# RAK3172_board.net
KiCad netlist of a schematic drawn in EAGLE
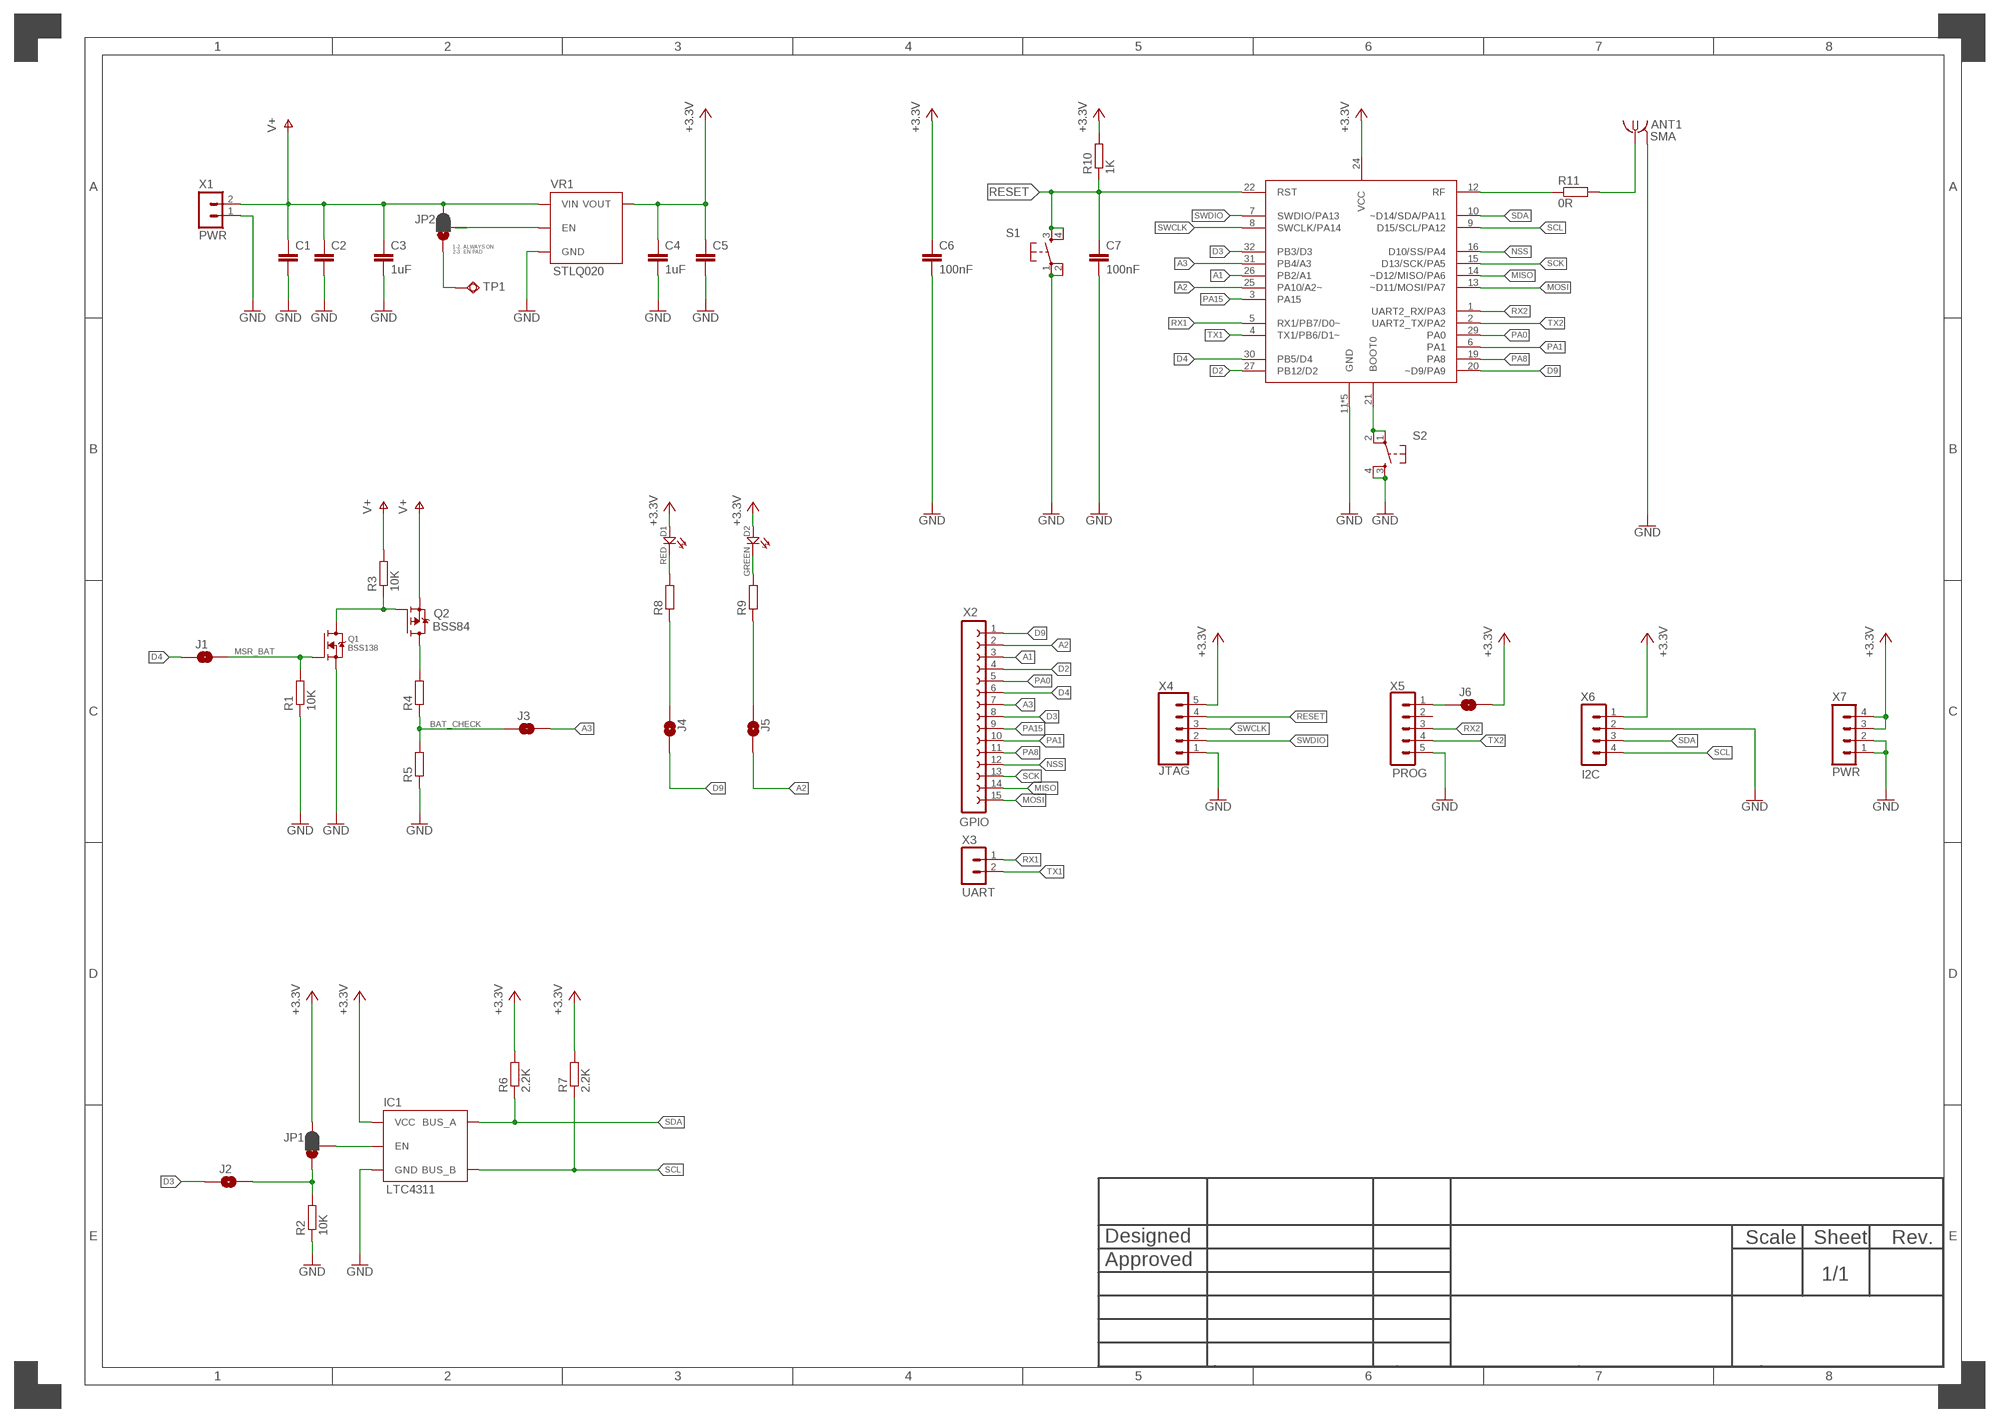
[diagram p0: schematic, sheet 1]

(export (version "E")
  (design (tool "Eeschema 10.0.6"))
  (components
    (comp (ref "ANT1")
      (value "SMA")
      (footprint "eagle-import:SMA_1MM")
      (libsource (lib "eagle-import") (part "SMA"))
    )
    (comp (ref "C1")
      (value "CAP_CERAMIC_0603")
      (footprint "eagle-import:SMD_0603C")
      (libsource (lib "eagle-import") (part "CAP_CERAMIC_0603"))
    )
    (comp (ref "C2")
      (value "CAP_CERAMIC_0603")
      (footprint "eagle-import:SMD_0603C")
      (libsource (lib "eagle-import") (part "CAP_CERAMIC_0603"))
    )
    (comp (ref "C3")
      (value "1uF")
      (footprint "eagle-import:SMD_0603C")
      (libsource (lib "eagle-import") (part "CAP_CERAMIC_0603"))
    )
    (comp (ref "C4")
      (value "1uF")
      (footprint "eagle-import:SMD_0603C")
      (libsource (lib "eagle-import") (part "CAP_CERAMIC_0603"))
    )
    (comp (ref "C5")
      (value "CAP_CERAMIC_0603")
      (footprint "eagle-import:SMD_0603C")
      (libsource (lib "eagle-import") (part "CAP_CERAMIC_0603"))
    )
    (comp (ref "C6")
      (value "100nF")
      (footprint "eagle-import:SMD_0603C")
      (libsource (lib "eagle-import") (part "CAP_CERAMIC_0603"))
    )
    (comp (ref "C7")
      (value "100nF")
      (footprint "eagle-import:SMD_0603C")
      (libsource (lib "eagle-import") (part "CAP_CERAMIC_0603"))
    )
    (comp (ref "D1")
      (value "RED")
      (footprint "eagle-import:LED-0805")
      (libsource (lib "eagle-import") (part "LED0805"))
    )
    (comp (ref "D2")
      (value "GREEN")
      (footprint "eagle-import:LED-0805")
      (libsource (lib "eagle-import") (part "LED0805"))
    )
    (comp (ref "IC1")
      (value "LTC4311")
      (footprint "eagle-import:SC-70-6")
      (libsource (lib "eagle-import") (part "LTC4311"))
    )
    (comp (ref "IC2")
      (value "RAK3172HF")
      (footprint "eagle-import:RAK3172")
      (libsource (lib "eagle-import") (part "RAK3172HF"))
    )
    (comp (ref "J1")
      (value "SMD_JUMP_2_NO_N")
      (footprint "eagle-import:SMT_JUMP_2_NO")
      (libsource (lib "eagle-import") (part "SMD_JUMP_2_NO_N"))
    )
    (comp (ref "J2")
      (value "SMD_JUMP_2_NO_N")
      (footprint "eagle-import:SMT_JUMP_2_NO")
      (libsource (lib "eagle-import") (part "SMD_JUMP_2_NO_N"))
    )
    (comp (ref "J3")
      (value "SMD_JUMP_2_NO_N")
      (footprint "eagle-import:SMT_JUMP_2_NO")
      (libsource (lib "eagle-import") (part "SMD_JUMP_2_NO_N"))
    )
    (comp (ref "J4")
      (value "SMD_JUMP_2_NO_N")
      (footprint "eagle-import:SMT_JUMP_2_NO")
      (libsource (lib "eagle-import") (part "SMD_JUMP_2_NO_N"))
    )
    (comp (ref "J5")
      (value "SMD_JUMP_2_NO_N")
      (footprint "eagle-import:SMT_JUMP_2_NO")
      (libsource (lib "eagle-import") (part "SMD_JUMP_2_NO_N"))
    )
    (comp (ref "J6")
      (value "SMD_JUMP_2_NO_N")
      (footprint "eagle-import:SMT_JUMP_2_NO")
      (libsource (lib "eagle-import") (part "SMD_JUMP_2_NO_N"))
    )
    (comp (ref "JP1")
      (value "JUMPER-SMT_3_1-NC_PASTE_SILK")
      (footprint "eagle-import:SMT-JUMPER_3_1-NC_PASTE_SILK")
      (libsource (lib "eagle-import") (part "JUMPER-SMT_3_1-NC_PASTE_SILK"))
    )
    (comp (ref "JP2")
      (value "JUMPER-SMT_3_1-NC_PASTE_SILK")
      (footprint "eagle-import:SMT-JUMPER_3_1-NC_PASTE_SILK")
      (libsource (lib "eagle-import") (part "JUMPER-SMT_3_1-NC_PASTE_SILK"))
    )
    (comp (ref "Q1")
      (value "BSS138")
      (footprint "eagle-import:SOT-23-3")
      (libsource (lib "eagle-import") (part "BSS138"))
    )
    (comp (ref "Q2")
      (value "BSS84")
      (footprint "eagle-import:SOT-23-3")
      (libsource (lib "eagle-import") (part "BSS84"))
    )
    (comp (ref "R1")
      (value "10K")
      (footprint "eagle-import:SMD_0603")
      (libsource (lib "eagle-import") (part "RESISTOR_0603"))
    )
    (comp (ref "R2")
      (value "10K")
      (footprint "eagle-import:SMD_0603")
      (libsource (lib "eagle-import") (part "RESISTOR_0603"))
    )
    (comp (ref "R3")
      (value "10K")
      (footprint "eagle-import:SMD_0603")
      (libsource (lib "eagle-import") (part "RESISTOR_0603"))
    )
    (comp (ref "R4")
      (value "RESISTOR_0603")
      (footprint "eagle-import:SMD_0603")
      (libsource (lib "eagle-import") (part "RESISTOR_0603"))
    )
    (comp (ref "R5")
      (value "RESISTOR_0603")
      (footprint "eagle-import:SMD_0603")
      (libsource (lib "eagle-import") (part "RESISTOR_0603"))
    )
    (comp (ref "R6")
      (value "2.2K")
      (footprint "eagle-import:SMD_0603")
      (libsource (lib "eagle-import") (part "RESISTOR_0603"))
    )
    (comp (ref "R7")
      (value "2.2K")
      (footprint "eagle-import:SMD_0603")
      (libsource (lib "eagle-import") (part "RESISTOR_0603"))
    )
    (comp (ref "R8")
      (value "RESISTOR_0603")
      (footprint "eagle-import:SMD_0603")
      (libsource (lib "eagle-import") (part "RESISTOR_0603"))
    )
    (comp (ref "R9")
      (value "RESISTOR_0603")
      (footprint "eagle-import:SMD_0603")
      (libsource (lib "eagle-import") (part "RESISTOR_0603"))
    )
    (comp (ref "R10")
      (value "1K")
      (footprint "eagle-import:SMD_0603")
      (libsource (lib "eagle-import") (part "RESISTOR_0603"))
    )
    (comp (ref "R11")
      (value "0R")
      (footprint "eagle-import:SMD_0603")
      (libsource (lib "eagle-import") (part "RESISTOR_0603"))
    )
    (comp (ref "S1")
      (value "BTNRKB2")
      (footprint "eagle-import:RKB2")
      (libsource (lib "eagle-import") (part "BTNRKB2"))
    )
    (comp (ref "S2")
      (value "BTNRKB2")
      (footprint "eagle-import:RKB2")
      (libsource (lib "eagle-import") (part "BTNRKB2"))
    )
    (comp (ref "TP1")
      (value "PAD1.5X3.0")
      (footprint "eagle-import:PAD1.5X3.0")
      (libsource (lib "eagle-import") (part "PAD1.5X3.0"))
    )
    (comp (ref "VR1")
      (value "STLQ020")
      (footprint "eagle-import:SOT323-5L")
      (libsource (lib "eagle-import") (part "STLQ020"))
    )
    (comp (ref "X1")
      (value "PWR")
      (footprint "eagle-import:JST-PH_2")
      (libsource (lib "eagle-import") (part "JST02_PH_H"))
    )
    (comp (ref "X2")
      (value "GPIO")
      (footprint "eagle-import:1X15")
      (libsource (lib "eagle-import") (part "CONN_15"))
    )
    (comp (ref "X3")
      (value "UART")
      (footprint "eagle-import:1X02")
      (libsource (lib "eagle-import") (part "CONN_02"))
    )
    (comp (ref "X4")
      (value "JTAG")
      (footprint "eagle-import:1X05_LOCK")
      (libsource (lib "eagle-import") (part "CONN_05LOCK"))
    )
    (comp (ref "X5")
      (value "PROG")
      (footprint "eagle-import:JST05_2MM")
      (libsource (lib "eagle-import") (part "JST05_2"))
    )
    (comp (ref "X6")
      (value "I2C")
      (footprint "eagle-import:JST-PH_4")
      (libsource (lib "eagle-import") (part "JST04_PH"))
    )
    (comp (ref "X7")
      (value "PWR")
      (footprint "eagle-import:2X02")
      (libsource (lib "eagle-import") (part "CONN_02X2"))
    )
  )
  (nets
    (net (code "1") (name "+3.3V") (class "Default")
      (node (ref "C4") (pin "1") (pinfunction "1_1") (pintype "passive"))
      (node (ref "C5") (pin "1") (pinfunction "1_1") (pintype "passive"))
      (node (ref "C6") (pin "1") (pinfunction "1_1") (pintype "passive"))
      (node (ref "D1") (pin "+") (pinfunction "+_+") (pintype "passive"))
      (node (ref "D2") (pin "+") (pinfunction "+_+") (pintype "passive"))
      (node (ref "IC1") (pin "P1") (pinfunction "VCC_P1") (pintype "power_in"))
      (node (ref "IC2") (pin "24") (pinfunction "VCC_24") (pintype "power_in"))
      (node (ref "J6") (pin "2") (pinfunction "2_2") (pintype "passive"))
      (node (ref "JP1") (pin "3") (pinfunction "3_3") (pintype "passive"))
      (node (ref "R10") (pin "2") (pinfunction "2_2") (pintype "passive"))
      (node (ref "R6") (pin "2") (pinfunction "2_2") (pintype "passive"))
      (node (ref "R7") (pin "2") (pinfunction "2_2") (pintype "passive"))
      (node (ref "VR1") (pin "P$5") (pinfunction "VOUT_P$5") (pintype "power_in"))
      (node (ref "X4") (pin "5") (pinfunction "5_5") (pintype "passive"))
      (node (ref "X6") (pin "1") (pinfunction "1_1") (pintype "passive"))
      (node (ref "X7") (pin "3") (pinfunction "3_3") (pintype "passive"))
      (node (ref "X7") (pin "4") (pinfunction "4_4") (pintype "passive"))
    )
    (net (code "2") (name "/BAT_CHECK") (class "Default")
      (node (ref "J3") (pin "1") (pinfunction "1_1") (pintype "passive"))
      (node (ref "R4") (pin "1") (pinfunction "1_1") (pintype "passive"))
      (node (ref "R5") (pin "2") (pinfunction "2_2") (pintype "passive"))
    )
    (net (code "3") (name "/MSR_BAT") (class "Default")
      (node (ref "J1") (pin "2") (pinfunction "2_2") (pintype "passive"))
      (node (ref "Q1") (pin "1") (pinfunction "G_1") (pintype "bidirectional"))
      (node (ref "R1") (pin "2") (pinfunction "2_2") (pintype "passive"))
    )
    (net (code "4") (name "A1") (class "Default")
      (node (ref "IC2") (pin "26") (pinfunction "PB2/A1_26") (pintype "bidirectional"))
      (node (ref "X2") (pin "3") (pinfunction "3_3") (pintype "passive"))
    )
    (net (code "5") (name "A2") (class "Default")
      (node (ref "IC2") (pin "25") (pinfunction "PA10/A2~{}_25") (pintype "bidirectional"))
      (node (ref "J5") (pin "2") (pinfunction "2_2") (pintype "passive"))
      (node (ref "X2") (pin "2") (pinfunction "2_2") (pintype "passive"))
    )
    (net (code "6") (name "A3") (class "Default")
      (node (ref "IC2") (pin "31") (pinfunction "PB4/A3_31") (pintype "bidirectional"))
      (node (ref "J3") (pin "2") (pinfunction "2_2") (pintype "passive"))
      (node (ref "X2") (pin "7") (pinfunction "7_7") (pintype "passive"))
    )
    (net (code "7") (name "D2") (class "Default")
      (node (ref "IC2") (pin "27") (pinfunction "PB12/D2_27") (pintype "bidirectional"))
      (node (ref "X2") (pin "4") (pinfunction "4_4") (pintype "passive"))
    )
    (net (code "8") (name "D3") (class "Default")
      (node (ref "IC2") (pin "32") (pinfunction "PB3/D3_32") (pintype "bidirectional"))
      (node (ref "J2") (pin "1") (pinfunction "1_1") (pintype "passive"))
      (node (ref "X2") (pin "8") (pinfunction "8_8") (pintype "passive"))
    )
    (net (code "9") (name "D4") (class "Default")
      (node (ref "IC2") (pin "30") (pinfunction "PB5/D4_30") (pintype "bidirectional"))
      (node (ref "J1") (pin "1") (pinfunction "1_1") (pintype "passive"))
      (node (ref "X2") (pin "6") (pinfunction "6_6") (pintype "passive"))
    )
    (net (code "10") (name "D9") (class "Default")
      (node (ref "IC2") (pin "20") (pinfunction "~{D9/PA9}_20") (pintype "bidirectional"))
      (node (ref "J4") (pin "2") (pinfunction "2_2") (pintype "passive"))
      (node (ref "X2") (pin "1") (pinfunction "1_1") (pintype "passive"))
    )
    (net (code "11") (name "GND") (class "Default")
      (node (ref "ANT1") (pin "G@1") (pinfunction "GND_G@1") (pintype "passive"))
      (node (ref "ANT1") (pin "G@2") (pinfunction "GND_G@2") (pintype "passive"))
      (node (ref "ANT1") (pin "G@3") (pinfunction "GND_G@3") (pintype "passive"))
      (node (ref "ANT1") (pin "G@4") (pinfunction "GND_G@4") (pintype "passive"))
      (node (ref "C1") (pin "2") (pinfunction "2_2") (pintype "passive"))
      (node (ref "C2") (pin "2") (pinfunction "2_2") (pintype "passive"))
      (node (ref "C3") (pin "2") (pinfunction "2_2") (pintype "passive"))
      (node (ref "C4") (pin "2") (pinfunction "2_2") (pintype "passive"))
      (node (ref "C5") (pin "2") (pinfunction "2_2") (pintype "passive"))
      (node (ref "C6") (pin "2") (pinfunction "2_2") (pintype "passive"))
      (node (ref "C7") (pin "2") (pinfunction "2_2") (pintype "passive"))
      (node (ref "IC1") (pin "P2") (pinfunction "GND_P2") (pintype "power_in"))
      (node (ref "IC1") (pin "P5") (pinfunction "GND_P5") (pintype "power_in"))
      (node (ref "IC2") (pin "11") (pinfunction "GND_11") (pintype "power_in"))
      (node (ref "IC2") (pin "17") (pinfunction "GND_17") (pintype "power_in"))
      (node (ref "IC2") (pin "18") (pinfunction "GND_18") (pintype "power_in"))
      (node (ref "IC2") (pin "23") (pinfunction "GND_23") (pintype "power_in"))
      (node (ref "IC2") (pin "28") (pinfunction "GND_28") (pintype "power_in"))
      (node (ref "Q1") (pin "2") (pinfunction "S_2") (pintype "bidirectional"))
      (node (ref "R1") (pin "1") (pinfunction "1_1") (pintype "passive"))
      (node (ref "R2") (pin "1") (pinfunction "1_1") (pintype "passive"))
      (node (ref "R5") (pin "1") (pinfunction "1_1") (pintype "passive"))
      (node (ref "S1") (pin "1") (pinfunction "P_1") (pintype "passive"))
      (node (ref "S1") (pin "2") (pinfunction "P1_2") (pintype "passive"))
      (node (ref "S2") (pin "3") (pinfunction "S_3") (pintype "passive"))
      (node (ref "S2") (pin "4") (pinfunction "S1_4") (pintype "passive"))
      (node (ref "VR1") (pin "P$2") (pinfunction "GND_P$2") (pintype "power_in"))
      (node (ref "X1") (pin "1") (pinfunction "1_1") (pintype "passive"))
      (node (ref "X4") (pin "1") (pinfunction "1_1") (pintype "passive"))
      (node (ref "X5") (pin "5") (pinfunction "5_5") (pintype "passive"))
      (node (ref "X6") (pin "2") (pinfunction "2_2") (pintype "passive"))
      (node (ref "X7") (pin "1") (pinfunction "1_1") (pintype "passive"))
      (node (ref "X7") (pin "2") (pinfunction "2_2") (pintype "passive"))
    )
    (net (code "12") (name "MISO") (class "Default")
      (node (ref "IC2") (pin "14") (pinfunction "~{D12/MISO/PA6}_14") (pintype "bidirectional"))
      (node (ref "X2") (pin "14") (pinfunction "14_14") (pintype "passive"))
    )
    (net (code "13") (name "MOSI") (class "Default")
      (node (ref "IC2") (pin "13") (pinfunction "~{D11/MOSI/PA7}_13") (pintype "bidirectional"))
      (node (ref "X2") (pin "15") (pinfunction "15_15") (pintype "passive"))
    )
    (net (code "14") (name "NSS") (class "Default")
      (node (ref "IC2") (pin "16") (pinfunction "D10/SS/PA4_16") (pintype "bidirectional"))
      (node (ref "X2") (pin "12") (pinfunction "12_12") (pintype "passive"))
    )
    (net (code "15") (name "Net-(ANT1-Pad1)") (class "Default")
      (node (ref "ANT1") (pin "1") (pinfunction "1_1") (pintype "passive"))
      (node (ref "R11") (pin "2") (pinfunction "2_2") (pintype "passive"))
    )
    (net (code "16") (name "Net-(D1-Pad-)") (class "Default")
      (node (ref "D1") (pin "-") (pinfunction "-_-") (pintype "passive"))
      (node (ref "R8") (pin "2") (pinfunction "2_2") (pintype "passive"))
    )
    (net (code "17") (name "Net-(D2-Pad-)") (class "Default")
      (node (ref "D2") (pin "-") (pinfunction "-_-") (pintype "passive"))
      (node (ref "R9") (pin "2") (pinfunction "2_2") (pintype "passive"))
    )
    (net (code "18") (name "Net-(IC1-EN)") (class "Default")
      (node (ref "IC1") (pin "P3") (pinfunction "EN_P3") (pintype "bidirectional"))
      (node (ref "JP1") (pin "2") (pinfunction "2_2") (pintype "passive"))
    )
    (net (code "19") (name "Net-(IC2-BOOT0)") (class "Default")
      (node (ref "IC2") (pin "21") (pinfunction "BOOT0_21") (pintype "input"))
      (node (ref "S2") (pin "1") (pinfunction "P_1") (pintype "passive"))
      (node (ref "S2") (pin "2") (pinfunction "P1_2") (pintype "passive"))
    )
    (net (code "20") (name "Net-(IC2-RF)") (class "Default")
      (node (ref "IC2") (pin "12") (pinfunction "RF_12") (pintype "output"))
      (node (ref "R11") (pin "1") (pinfunction "1_1") (pintype "passive"))
    )
    (net (code "21") (name "Net-(J2-Pad2)") (class "Default")
      (node (ref "J2") (pin "2") (pinfunction "2_2") (pintype "passive"))
      (node (ref "JP1") (pin "1") (pinfunction "1_1") (pintype "passive"))
      (node (ref "R2") (pin "2") (pinfunction "2_2") (pintype "passive"))
    )
    (net (code "22") (name "Net-(J4-Pad1)") (class "Default")
      (node (ref "J4") (pin "1") (pinfunction "1_1") (pintype "passive"))
      (node (ref "R8") (pin "1") (pinfunction "1_1") (pintype "passive"))
    )
    (net (code "23") (name "Net-(J5-Pad1)") (class "Default")
      (node (ref "J5") (pin "1") (pinfunction "1_1") (pintype "passive"))
      (node (ref "R9") (pin "1") (pinfunction "1_1") (pintype "passive"))
    )
    (net (code "24") (name "Net-(J6-Pad1)") (class "Default")
      (node (ref "J6") (pin "1") (pinfunction "1_1") (pintype "passive"))
      (node (ref "X5") (pin "1") (pinfunction "1_1") (pintype "passive"))
    )
    (net (code "25") (name "Net-(JP2-Pad1)") (class "Default")
      (node (ref "JP2") (pin "1") (pinfunction "1_1") (pintype "passive"))
      (node (ref "TP1") (pin "P$1") (pinfunction "P$1_P$1") (pintype "bidirectional"))
    )
    (net (code "26") (name "Net-(Q1-D)") (class "Default")
      (node (ref "Q1") (pin "3") (pinfunction "D_3") (pintype "bidirectional"))
      (node (ref "Q2") (pin "1") (pinfunction "G_1") (pintype "passive"))
      (node (ref "R3") (pin "1") (pinfunction "1_1") (pintype "passive"))
    )
    (net (code "27") (name "Net-(Q2-D)") (class "Default")
      (node (ref "Q2") (pin "3") (pinfunction "D_3") (pintype "passive"))
      (node (ref "R4") (pin "2") (pinfunction "2_2") (pintype "passive"))
    )
    (net (code "28") (name "Net-(VR1-EN)") (class "Default")
      (node (ref "JP2") (pin "2") (pinfunction "2_2") (pintype "passive"))
      (node (ref "VR1") (pin "P$3") (pinfunction "EN_P$3") (pintype "bidirectional"))
    )
    (net (code "29") (name "PA0") (class "Default")
      (node (ref "IC2") (pin "29") (pinfunction "PA0_29") (pintype "bidirectional"))
      (node (ref "X2") (pin "5") (pinfunction "5_5") (pintype "passive"))
    )
    (net (code "30") (name "PA1") (class "Default")
      (node (ref "IC2") (pin "6") (pinfunction "PA1_6") (pintype "bidirectional"))
      (node (ref "X2") (pin "10") (pinfunction "10_10") (pintype "passive"))
    )
    (net (code "31") (name "PA8") (class "Default")
      (node (ref "IC2") (pin "19") (pinfunction "PA8_19") (pintype "bidirectional"))
      (node (ref "X2") (pin "11") (pinfunction "11_11") (pintype "passive"))
    )
    (net (code "32") (name "PA15") (class "Default")
      (node (ref "IC2") (pin "3") (pinfunction "PA15_3") (pintype "bidirectional"))
      (node (ref "X2") (pin "9") (pinfunction "9_9") (pintype "passive"))
    )
    (net (code "33") (name "RESET") (class "Default")
      (node (ref "C7") (pin "1") (pinfunction "1_1") (pintype "passive"))
      (node (ref "IC2") (pin "22") (pinfunction "RST_22") (pintype "input"))
      (node (ref "R10") (pin "1") (pinfunction "1_1") (pintype "passive"))
      (node (ref "S1") (pin "3") (pinfunction "S_3") (pintype "passive"))
      (node (ref "S1") (pin "4") (pinfunction "S1_4") (pintype "passive"))
      (node (ref "X4") (pin "4") (pinfunction "4_4") (pintype "passive"))
    )
    (net (code "34") (name "RX1") (class "Default")
      (node (ref "IC2") (pin "5") (pinfunction "RX1/PB7/D0~{}_5") (pintype "bidirectional"))
      (node (ref "X3") (pin "1") (pinfunction "1_1") (pintype "passive"))
    )
    (net (code "35") (name "RX2") (class "Default")
      (node (ref "IC2") (pin "1") (pinfunction "UART2_RX/PA3_1") (pintype "bidirectional"))
      (node (ref "X5") (pin "3") (pinfunction "3_3") (pintype "passive"))
    )
    (net (code "36") (name "SCK") (class "Default")
      (node (ref "IC2") (pin "15") (pinfunction "D13/SCK/PA5_15") (pintype "bidirectional"))
      (node (ref "X2") (pin "13") (pinfunction "13_13") (pintype "passive"))
    )
    (net (code "37") (name "SCL") (class "Default")
      (node (ref "IC1") (pin "P6") (pinfunction "BUS_B_P6") (pintype "power_in"))
      (node (ref "IC2") (pin "9") (pinfunction "D15/SCL/PA12_9") (pintype "bidirectional"))
      (node (ref "R7") (pin "1") (pinfunction "1_1") (pintype "passive"))
      (node (ref "X6") (pin "4") (pinfunction "4_4") (pintype "passive"))
    )
    (net (code "38") (name "SDA") (class "Default")
      (node (ref "IC1") (pin "P4") (pinfunction "BUS_A_P4") (pintype "power_in"))
      (node (ref "IC2") (pin "10") (pinfunction "~{D14/SDA/PA11}_10") (pintype "bidirectional"))
      (node (ref "R6") (pin "1") (pinfunction "1_1") (pintype "passive"))
      (node (ref "X6") (pin "3") (pinfunction "3_3") (pintype "passive"))
    )
    (net (code "39") (name "SWCLK") (class "Default")
      (node (ref "IC2") (pin "8") (pinfunction "SWCLK/PA14_8") (pintype "bidirectional"))
      (node (ref "X4") (pin "3") (pinfunction "3_3") (pintype "passive"))
    )
    (net (code "40") (name "SWDIO") (class "Default")
      (node (ref "IC2") (pin "7") (pinfunction "SWDIO/PA13_7") (pintype "bidirectional"))
      (node (ref "X4") (pin "2") (pinfunction "2_2") (pintype "passive"))
    )
    (net (code "41") (name "TX1") (class "Default")
      (node (ref "IC2") (pin "4") (pinfunction "TX1/PB6/D1~{}_4") (pintype "bidirectional"))
      (node (ref "X3") (pin "2") (pinfunction "2_2") (pintype "passive"))
    )
    (net (code "42") (name "TX2") (class "Default")
      (node (ref "IC2") (pin "2") (pinfunction "UART2_TX/PA2_2") (pintype "bidirectional"))
      (node (ref "X5") (pin "4") (pinfunction "4_4") (pintype "passive"))
    )
    (net (code "43") (name "V+") (class "Default")
      (node (ref "C1") (pin "1") (pinfunction "1_1") (pintype "passive"))
      (node (ref "C2") (pin "1") (pinfunction "1_1") (pintype "passive"))
      (node (ref "C3") (pin "1") (pinfunction "1_1") (pintype "passive"))
      (node (ref "JP2") (pin "3") (pinfunction "3_3") (pintype "passive"))
      (node (ref "Q2") (pin "2") (pinfunction "S_2") (pintype "passive"))
      (node (ref "R3") (pin "2") (pinfunction "2_2") (pintype "passive"))
      (node (ref "VR1") (pin "P$1") (pinfunction "VIN_P$1") (pintype "power_in"))
      (node (ref "X1") (pin "2") (pinfunction "2_2") (pintype "passive"))
    )
    (net (code "44") (name "unconnected-(X5-Pad2)") (class "Default")
      (node (ref "X5") (pin "2") (pinfunction "2_2") (pintype "passive"))
    )
  )
)
